# Power.net
KiCad netlist of a schematic drawn in Altium Designer
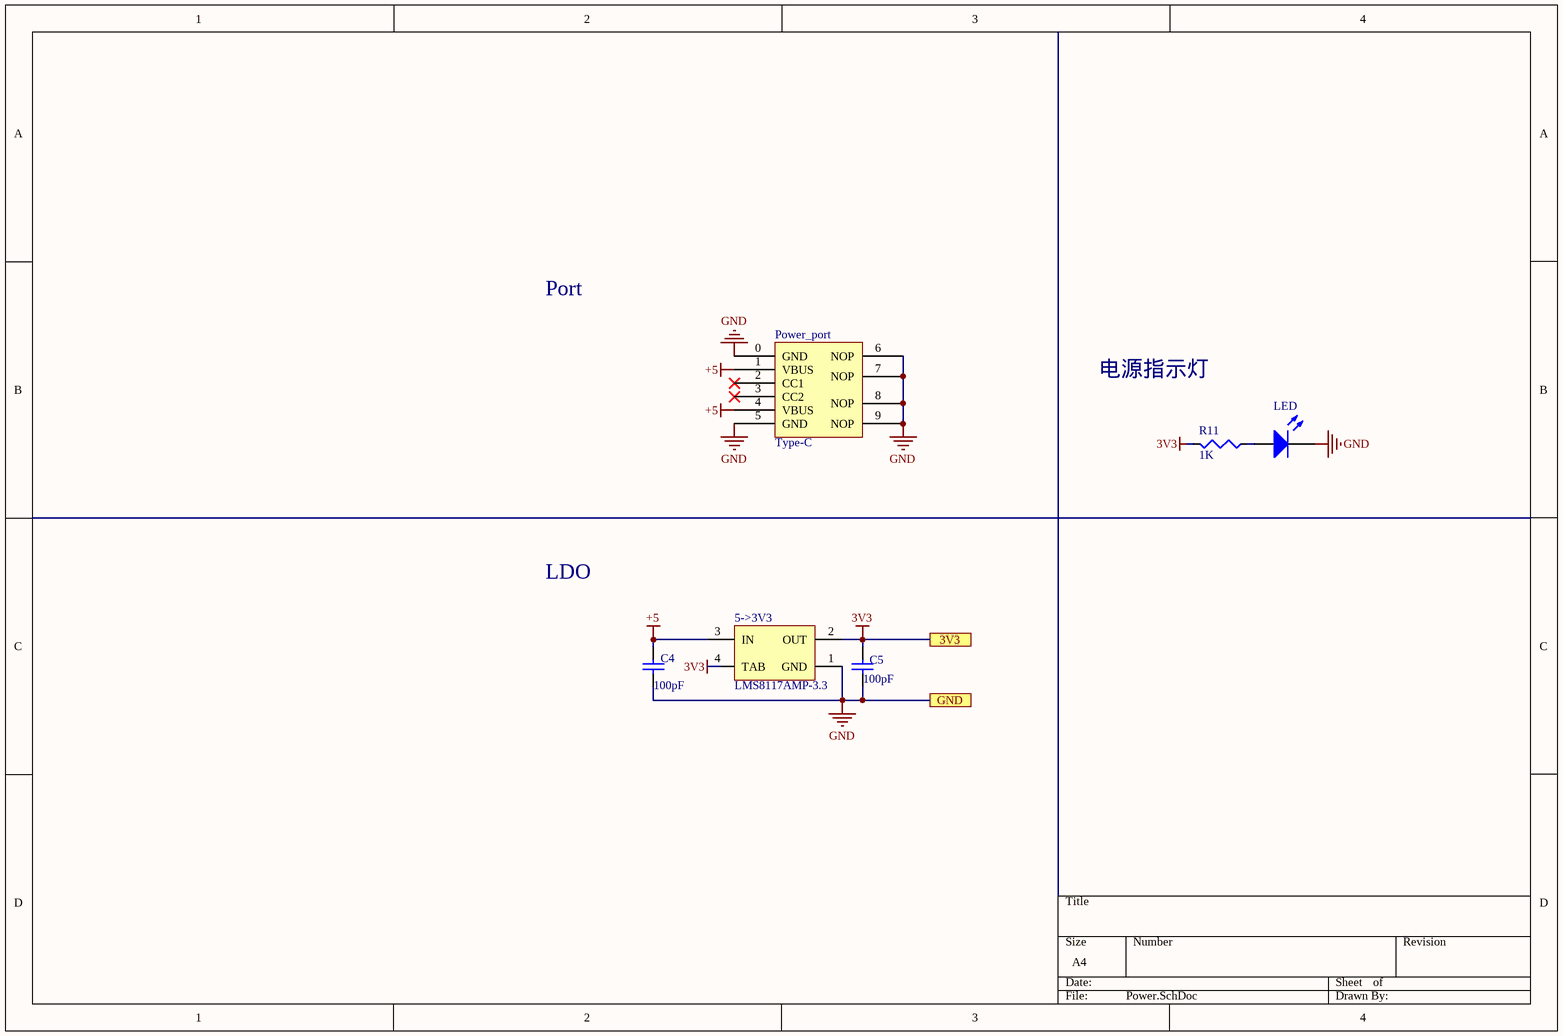
[diagram p0: Power.SchDoc]

(export (version "E")
  (design (tool "Eeschema 10.0.6"))
  (components
    (comp (ref "5->3V3")
      (value "LMS8117AMP-3.3")
      (footprint "MP04A_N")
      (description "1A Low-Dropout Linear Regulator, 4-pin SOT-223")
      (fields (field (name "MANUFACTURER") "National Semiconductor"))
      (libsource (lib "National Semiconductor LDO") (part "LMS8117AMP-3.3"))
    )
    (comp (ref "C4")
      (value "100pF")
      (footprint "6-0805_N")
      (description "Capacitor")
      (fields (field (name "Comment") "Cap") (field (name "PUBLISHER") "Altium Limited"))
      (libsource (lib "Miscellaneous Devices") (part "Cap"))
    )
    (comp (ref "C5")
      (value "100pF")
      (footprint "6-0805_N")
      (description "Capacitor")
      (fields (field (name "Comment") "Cap") (field (name "PUBLISHER") "Altium Limited"))
      (libsource (lib "Miscellaneous Devices") (part "Cap"))
    )
    (comp (ref "LED")
      (value "LED3")
      (footprint "Miscellaneous Devices:6-0805_N")
      (description "Typical BLUE SiC LED")
      (fields (field (name "PUBLISHER") "Altium Limited"))
      (libsource (lib "Miscellaneous Devices") (part "LED3"))
    )
    (comp (ref "Power_port")
      (value "Type-C")
      (footprint "Tpye-C")
      (libsource (lib "Type-C_6pin") (part "Type-C"))
    )
    (comp (ref "R11")
      (value "1K")
      (footprint "6-0805_N")
      (description "Resistor")
      (fields (field (name "Comment") "Res3") (field (name "PUBLISHER") "Altium Limited"))
      (libsource (lib "Miscellaneous Devices") (part "Res3"))
    )
  )
  (nets
    (net (code "1") (name "+5") (class "Default")
      (node (ref "5->3V3") (pin "3") (pinfunction "IN_3") (pintype "power_in"))
      (node (ref "C4") (pin "2") (pinfunction "2_2") (pintype "passive"))
      (node (ref "Power_port") (pin "1") (pinfunction "VBUS_1") (pintype "passive"))
      (node (ref "Power_port") (pin "4") (pinfunction "VBUS_4") (pintype "passive"))
    )
    (net (code "2") (name "3V3") (class "Default")
      (node (ref "5->3V3") (pin "2") (pinfunction "OUT_2") (pintype "power_in"))
      (node (ref "5->3V3") (pin "4") (pinfunction "TAB_4") (pintype "power_in"))
      (node (ref "C5") (pin "2") (pinfunction "2_2") (pintype "passive"))
      (node (ref "R11") (pin "2") (pinfunction "2_2") (pintype "passive"))
    )
    (net (code "3") (name "GND") (class "Default")
      (node (ref "5->3V3") (pin "1") (pinfunction "GND_1") (pintype "power_in"))
      (node (ref "C4") (pin "1") (pinfunction "1_1") (pintype "passive"))
      (node (ref "C5") (pin "1") (pinfunction "1_1") (pintype "passive"))
      (node (ref "LED") (pin "2") (pinfunction "K_2") (pintype "passive"))
      (node (ref "Power_port") (pin "0") (pinfunction "GND_0") (pintype "passive"))
      (node (ref "Power_port") (pin "5") (pinfunction "GND_5") (pintype "passive"))
      (node (ref "Power_port") (pin "6") (pinfunction "NOP_6") (pintype "passive"))
      (node (ref "Power_port") (pin "7") (pinfunction "NOP_7") (pintype "passive"))
      (node (ref "Power_port") (pin "8") (pinfunction "NOP_8") (pintype "passive"))
      (node (ref "Power_port") (pin "9") (pinfunction "NOP_9") (pintype "passive"))
    )
    (net (code "4") (name "Net-(LED-A)") (class "Default")
      (node (ref "LED") (pin "1") (pinfunction "A_1") (pintype "passive"))
      (node (ref "R11") (pin "1") (pinfunction "1_1") (pintype "passive"))
    )
    (net (code "5") (name "unconnected-(Power_port-CC1-Pad2)") (class "Default")
      (node (ref "Power_port") (pin "2") (pinfunction "CC1_2") (pintype "passive+no_connect"))
    )
    (net (code "6") (name "unconnected-(Power_port-CC2-Pad3)") (class "Default")
      (node (ref "Power_port") (pin "3") (pinfunction "CC2_3") (pintype "passive+no_connect"))
    )
  )
)
